# XICIE_AFE_SMD_revC.net
KiCad netlist of a schematic drawn in EAGLE
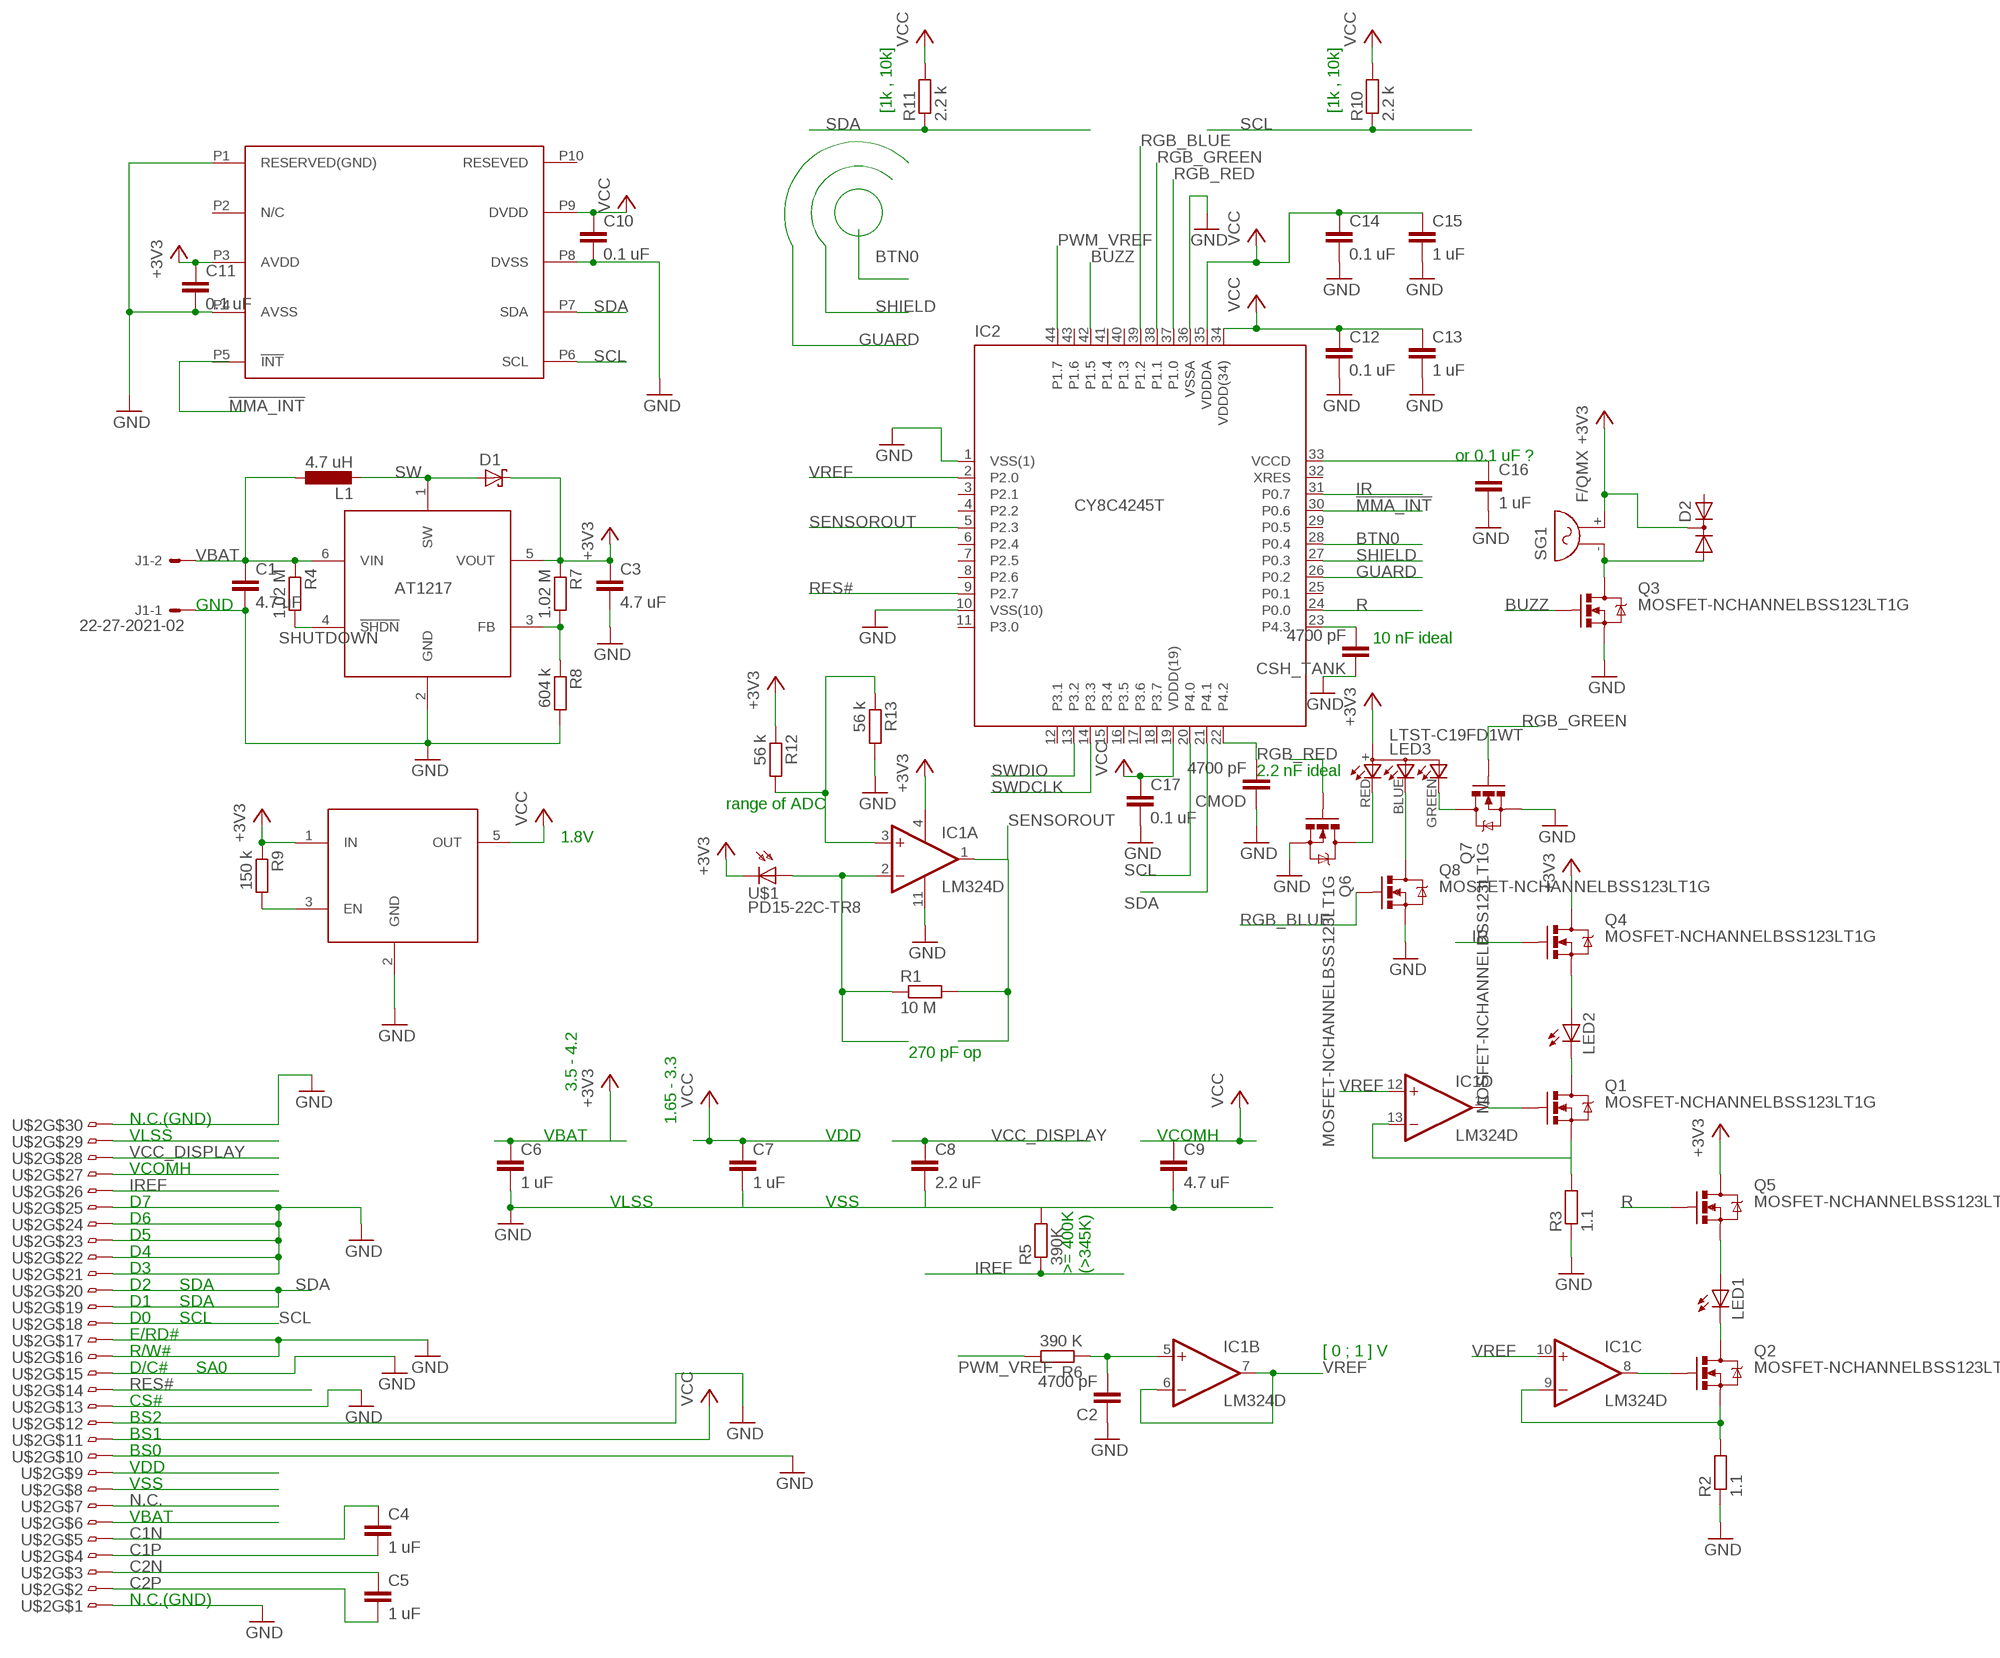
[diagram p0: schematic, sheet 1]

(export (version "E")
  (design (tool "Eeschema 10.0.6"))
  (components
    (comp (ref "C1")
      (value "4.7 uF")
      (footprint "eagle-import:C0603")
      (libsource (lib "eagle-import") (part "C-EUC0603"))
    )
    (comp (ref "C2")
      (value "4700 pF")
      (footprint "eagle-import:C0402")
      (libsource (lib "eagle-import") (part "C-EUC0402"))
    )
    (comp (ref "C3")
      (value "4.7 uF")
      (footprint "eagle-import:C0603")
      (libsource (lib "eagle-import") (part "C-EUC0603"))
    )
    (comp (ref "C4")
      (value "1 uF")
      (footprint "eagle-import:C0402")
      (libsource (lib "eagle-import") (part "C-EUC0402"))
    )
    (comp (ref "C5")
      (value "1 uF")
      (footprint "eagle-import:C0402")
      (libsource (lib "eagle-import") (part "C-EUC0402"))
    )
    (comp (ref "C6")
      (value "1 uF")
      (footprint "eagle-import:C0402")
      (libsource (lib "eagle-import") (part "C-EUC0402"))
    )
    (comp (ref "C7")
      (value "1 uF")
      (footprint "eagle-import:C0402")
      (libsource (lib "eagle-import") (part "C-EUC0402"))
    )
    (comp (ref "C8")
      (value "2.2 uF")
      (footprint "eagle-import:C0603")
      (libsource (lib "eagle-import") (part "C-EUC0603"))
    )
    (comp (ref "C9")
      (value "4.7 uF")
      (footprint "eagle-import:C0603")
      (libsource (lib "eagle-import") (part "C-EUC0603"))
    )
    (comp (ref "C10")
      (value "0.1 uF")
      (footprint "eagle-import:C0402")
      (libsource (lib "eagle-import") (part "C-EUC0402"))
    )
    (comp (ref "C11")
      (value "0.1 uF")
      (footprint "eagle-import:C0402")
      (libsource (lib "eagle-import") (part "C-EUC0402"))
    )
    (comp (ref "C12")
      (value "0.1 uF")
      (footprint "eagle-import:C0402")
      (libsource (lib "eagle-import") (part "C-EUC0402"))
    )
    (comp (ref "C13")
      (value "1 uF")
      (footprint "eagle-import:C0402")
      (libsource (lib "eagle-import") (part "C-EUC0402"))
    )
    (comp (ref "C14")
      (value "0.1 uF")
      (footprint "eagle-import:C0402")
      (libsource (lib "eagle-import") (part "C-EUC0402"))
    )
    (comp (ref "C15")
      (value "1 uF")
      (footprint "eagle-import:C0402")
      (libsource (lib "eagle-import") (part "C-EUC0402"))
    )
    (comp (ref "C16")
      (value "1 uF")
      (footprint "eagle-import:C0402")
      (libsource (lib "eagle-import") (part "C-EUC0402"))
    )
    (comp (ref "C17")
      (value "0.1 uF")
      (footprint "eagle-import:C0402")
      (libsource (lib "eagle-import") (part "C-EUC0402"))
    )
    (comp (ref "CMOD")
      (value "4700 pF")
      (footprint "eagle-import:C0402")
      (libsource (lib "eagle-import") (part "C-EUC0402"))
    )
    (comp (ref "CSH_TANK")
      (value "4700 pF")
      (footprint "eagle-import:C0402")
      (libsource (lib "eagle-import") (part "C-EUC0402"))
    )
    (comp (ref "D1")
      (value "SCHOTTKY-DIODESMD")
      (footprint "eagle-import:SMINI2-F5-B")
      (libsource (lib "eagle-import") (part "SCHOTTKY-DIODESMD"))
    )
    (comp (ref "D2")
      (value "DIODE-2AC|CASOT23")
      (footprint "eagle-import:SOT23")
      (libsource (lib "eagle-import") (part "DIODE-2AC|CASOT23"))
    )
    (comp (ref "IC1")
      (value "LM324D")
      (footprint "eagle-import:SO14")
      (libsource (lib "eagle-import") (part "LM324D"))
    )
    (comp (ref "IC2")
      (value "CY8C4245T")
      (footprint "eagle-import:TQFP44")
      (libsource (lib "eagle-import") (part "CY8C4245T"))
    )
    (comp (ref "IC3")
      (value "AAT1217")
      (footprint "eagle-import:SOT23-6")
      (libsource (lib "eagle-import") (part "AAT1217"))
    )
    (comp (ref "J1")
      (value "22-27-2021-02")
      (footprint "eagle-import:6410-02")
      (libsource (lib "eagle-import") (part "22-?-0227-2021"))
    )
    (comp (ref "L1")
      (value "4.7 uH")
      (footprint "eagle-import:L2518")
      (libsource (lib "eagle-import") (part "L-EU"))
    )
    (comp (ref "LED1")
      (value "LED5MM")
      (footprint "eagle-import:LED5MM")
      (libsource (lib "eagle-import") (part "LED5MM"))
    )
    (comp (ref "LED2")
      (value "LED5MM")
      (footprint "eagle-import:LED5MM")
      (libsource (lib "eagle-import") (part "LED5MM"))
    )
    (comp (ref "LED3")
      (value "LTST-C19FD1WT")
      (footprint "eagle-import:GM1WA55311A")
      (libsource (lib "eagle-import") (part "LTST-C19FD1WT"))
    )
    (comp (ref "Q1")
      (value "MOSFET-NCHANNELBSS123LT1G")
      (footprint "eagle-import:SOT23")
      (libsource (lib "eagle-import") (part "MOSFET-NCHANNELBSS123LT1G"))
    )
    (comp (ref "Q2")
      (value "MOSFET-NCHANNELBSS123LT1G")
      (footprint "eagle-import:SOT23")
      (libsource (lib "eagle-import") (part "MOSFET-NCHANNELBSS123LT1G"))
    )
    (comp (ref "Q3")
      (value "MOSFET-NCHANNELBSS123LT1G")
      (footprint "eagle-import:SOT23")
      (libsource (lib "eagle-import") (part "MOSFET-NCHANNELBSS123LT1G"))
    )
    (comp (ref "Q4")
      (value "MOSFET-NCHANNELBSS123LT1G")
      (footprint "eagle-import:SOT23")
      (libsource (lib "eagle-import") (part "MOSFET-NCHANNELBSS123LT1G"))
    )
    (comp (ref "Q5")
      (value "MOSFET-NCHANNELBSS123LT1G")
      (footprint "eagle-import:SOT23")
      (libsource (lib "eagle-import") (part "MOSFET-NCHANNELBSS123LT1G"))
    )
    (comp (ref "Q6")
      (value "MOSFET-NCHANNELBSS123LT1G")
      (footprint "eagle-import:SOT23")
      (libsource (lib "eagle-import") (part "MOSFET-NCHANNELBSS123LT1G"))
    )
    (comp (ref "Q7")
      (value "MOSFET-NCHANNELBSS123LT1G")
      (footprint "eagle-import:SOT23")
      (libsource (lib "eagle-import") (part "MOSFET-NCHANNELBSS123LT1G"))
    )
    (comp (ref "Q8")
      (value "MOSFET-NCHANNELBSS123LT1G")
      (footprint "eagle-import:SOT23")
      (libsource (lib "eagle-import") (part "MOSFET-NCHANNELBSS123LT1G"))
    )
    (comp (ref "R1")
      (value "10 M")
      (footprint "eagle-import:R0402")
      (libsource (lib "eagle-import") (part "R-EU_R0402"))
    )
    (comp (ref "R2")
      (value "1.1")
      (footprint "eagle-import:R0402")
      (libsource (lib "eagle-import") (part "R-EU_R0402"))
    )
    (comp (ref "R3")
      (value "1.1")
      (footprint "eagle-import:R0402")
      (libsource (lib "eagle-import") (part "R-EU_R0402"))
    )
    (comp (ref "R4")
      (value "1.02 M")
      (footprint "eagle-import:R0805")
      (libsource (lib "eagle-import") (part "R-EU_R0805"))
    )
    (comp (ref "R5")
      (value "390K")
      (footprint "eagle-import:R0603")
      (libsource (lib "eagle-import") (part "resistor_R-EU_R0603"))
    )
    (comp (ref "R6")
      (value "390 K")
      (footprint "eagle-import:R0603")
      (libsource (lib "eagle-import") (part "R-EU_R0603"))
    )
    (comp (ref "R7")
      (value "1.02 M")
      (footprint "eagle-import:R0805")
      (libsource (lib "eagle-import") (part "R-EU_R0805"))
    )
    (comp (ref "R8")
      (value "604 k")
      (footprint "eagle-import:R0603")
      (libsource (lib "eagle-import") (part "R-EU_R0603"))
    )
    (comp (ref "R9")
      (value "150 k")
      (footprint "eagle-import:R0603")
      (libsource (lib "eagle-import") (part "R-EU_R0603"))
    )
    (comp (ref "R10")
      (value "2.2 k")
      (footprint "eagle-import:R0402")
      (libsource (lib "eagle-import") (part "R-EU_R0402"))
    )
    (comp (ref "R11")
      (value "2.2 k")
      (footprint "eagle-import:R0402")
      (libsource (lib "eagle-import") (part "R-EU_R0402"))
    )
    (comp (ref "R12")
      (value "56 k")
      (footprint "eagle-import:R0603")
      (libsource (lib "eagle-import") (part "R-EU_R0603"))
    )
    (comp (ref "R13")
      (value "56 k")
      (footprint "eagle-import:R0603")
      (libsource (lib "eagle-import") (part "R-EU_R0603"))
    )
    (comp (ref "SG1")
      (value "F/QMX")
      (footprint "eagle-import:F_QMX")
      (libsource (lib "eagle-import") (part "F/QMX"))
    )
    (comp (ref "U$1")
      (value "PD15-22C-TR8")
      (footprint "eagle-import:PHOTO_SMD")
      (libsource (lib "eagle-import") (part "PD15-22C-TR8"))
    )
    (comp (ref "U$2")
      (value "ER-OLED0.96")
      (footprint "eagle-import:FLEX0.7X30")
      (libsource (lib "eagle-import") (part "ER-OLED0.96"))
    )
    (comp (ref "U$3")
      (value "AAT3221")
      (footprint "eagle-import:SOT23-5")
      (libsource (lib "eagle-import") (part "AAT3221"))
    )
    (comp (ref "U$4")
      (value "MMA7660FC")
      (footprint "eagle-import:DFN10")
      (libsource (lib "eagle-import") (part "MMA7660FC"))
    )
  )
  (nets
    (net (code "1") (name "+3V3") (class "Default")
      (node (ref "C11") (pin "1") (pinfunction "1_1") (pintype "passive"))
      (node (ref "C3") (pin "1") (pinfunction "1_1") (pintype "passive"))
      (node (ref "C6") (pin "1") (pinfunction "1_1") (pintype "passive"))
      (node (ref "D1") (pin "C") (pinfunction "C_C") (pintype "passive"))
      (node (ref "D2") (pin "3") (pinfunction "C_3") (pintype "passive"))
      (node (ref "IC1") (pin "4") (pinfunction "V+_4") (pintype "power_in"))
      (node (ref "IC3") (pin "5") (pinfunction "VOUT_5") (pintype "bidirectional"))
      (node (ref "LED3") (pin "+") (pinfunction "A_+") (pintype "passive"))
      (node (ref "Q4") (pin "3") (pinfunction "D_3") (pintype "passive"))
      (node (ref "Q5") (pin "3") (pinfunction "D_3") (pintype "passive"))
      (node (ref "R12") (pin "1") (pinfunction "1_1") (pintype "passive"))
      (node (ref "R7") (pin "1") (pinfunction "1_1") (pintype "passive"))
      (node (ref "R9") (pin "1") (pinfunction "1_1") (pintype "passive"))
      (node (ref "SG1") (pin "+") (pinfunction "2_+") (pintype "passive"))
      (node (ref "U$1") (pin "CATHODE1") (pinfunction "C_CATHODE1") (pintype "passive"))
      (node (ref "U$1") (pin "CATHODE2") (pinfunction "C_CATHODE2") (pintype "passive"))
      (node (ref "U$2") (pin "P6") (pinfunction "1_P6") (pintype "passive"))
      (node (ref "U$3") (pin "1") (pinfunction "IN_1") (pintype "bidirectional"))
      (node (ref "U$4") (pin "P3") (pinfunction "AVDD_P3") (pintype "bidirectional"))
    )
    (net (code "2") (name "/BTN0") (class "Default")
      (node (ref "IC2") (pin "28") (pinfunction "P0.4_28") (pintype "bidirectional"))
    )
    (net (code "3") (name "/BUZZ") (class "Default")
      (node (ref "IC2") (pin "42") (pinfunction "P1.5_42") (pintype "bidirectional"))
      (node (ref "Q3") (pin "1") (pinfunction "G_1") (pintype "passive"))
    )
    (net (code "4") (name "/C1N") (class "Default")
      (node (ref "C4") (pin "1") (pinfunction "1_1") (pintype "passive"))
      (node (ref "U$2") (pin "P5") (pinfunction "1_P5") (pintype "passive"))
    )
    (net (code "5") (name "/C1P") (class "Default")
      (node (ref "C4") (pin "2") (pinfunction "2_2") (pintype "passive"))
      (node (ref "U$2") (pin "P4") (pinfunction "1_P4") (pintype "passive"))
    )
    (net (code "6") (name "/C2N") (class "Default")
      (node (ref "C5") (pin "1") (pinfunction "1_1") (pintype "passive"))
      (node (ref "U$2") (pin "P3") (pinfunction "1_P3") (pintype "passive"))
    )
    (net (code "7") (name "/C2P") (class "Default")
      (node (ref "C5") (pin "2") (pinfunction "2_2") (pintype "passive"))
      (node (ref "U$2") (pin "P2") (pinfunction "1_P2") (pintype "passive"))
    )
    (net (code "8") (name "/GUARD") (class "Default")
      (node (ref "IC2") (pin "26") (pinfunction "P0.2_26") (pintype "input"))
    )
    (net (code "9") (name "/IR") (class "Default")
      (node (ref "IC2") (pin "31") (pinfunction "P0.7_31") (pintype "bidirectional"))
      (node (ref "Q4") (pin "1") (pinfunction "G_1") (pintype "passive"))
    )
    (net (code "10") (name "/IREF") (class "Default")
      (node (ref "R5") (pin "1") (pinfunction "1_1") (pintype "passive"))
      (node (ref "U$2") (pin "P26") (pinfunction "1_P26") (pintype "passive"))
    )
    (net (code "11") (name "/N.C.") (class "Default")
      (node (ref "U$2") (pin "P7") (pinfunction "1_P7") (pintype "passive"))
    )
    (net (code "12") (name "/P2.2") (class "Default")
      (node (ref "IC2") (pin "4") (pinfunction "P2.2_4") (pintype "power_in"))
    )
    (net (code "13") (name "/P2.6") (class "Default")
      (node (ref "IC2") (pin "8") (pinfunction "P2.6_8") (pintype "power_in"))
    )
    (net (code "14") (name "/P3.6") (class "Default")
      (node (ref "IC2") (pin "17") (pinfunction "P3.6_17") (pintype "power_in"))
    )
    (net (code "15") (name "/PWM_VREF") (class "Default")
      (node (ref "IC2") (pin "44") (pinfunction "P1.7_44") (pintype "bidirectional"))
      (node (ref "R6") (pin "2") (pinfunction "2_2") (pintype "passive"))
    )
    (net (code "16") (name "/R") (class "Default")
      (node (ref "IC2") (pin "24") (pinfunction "P0.0_24") (pintype "bidirectional"))
      (node (ref "Q5") (pin "1") (pinfunction "G_1") (pintype "passive"))
    )
    (net (code "17") (name "/RES#") (class "Default")
      (node (ref "IC2") (pin "9") (pinfunction "P2.7_9") (pintype "bidirectional"))
      (node (ref "U$2") (pin "P14") (pinfunction "1_P14") (pintype "passive"))
    )
    (net (code "18") (name "/RGB_BLUE") (class "Default")
      (node (ref "IC2") (pin "39") (pinfunction "P1.2_39") (pintype "power_in"))
      (node (ref "Q8") (pin "1") (pinfunction "G_1") (pintype "passive"))
    )
    (net (code "19") (name "/RGB_GREEN") (class "Default")
      (node (ref "IC2") (pin "38") (pinfunction "P1.1_38") (pintype "bidirectional"))
      (node (ref "Q7") (pin "1") (pinfunction "G_1") (pintype "passive"))
    )
    (net (code "20") (name "/RGB_RED") (class "Default")
      (node (ref "IC2") (pin "37") (pinfunction "P1.0_37") (pintype "bidirectional"))
      (node (ref "Q6") (pin "1") (pinfunction "G_1") (pintype "passive"))
    )
    (net (code "21") (name "/SCL") (class "Default")
      (node (ref "IC2") (pin "20") (pinfunction "P4.0_20") (pintype "bidirectional"))
      (node (ref "R10") (pin "1") (pinfunction "1_1") (pintype "passive"))
      (node (ref "U$2") (pin "P18") (pinfunction "1_P18") (pintype "passive"))
      (node (ref "U$4") (pin "P6") (pinfunction "SCL_P6") (pintype "bidirectional"))
    )
    (net (code "22") (name "/SDA") (class "Default")
      (node (ref "IC2") (pin "21") (pinfunction "P4.1_21") (pintype "bidirectional"))
      (node (ref "R11") (pin "1") (pinfunction "1_1") (pintype "passive"))
      (node (ref "U$2") (pin "P19") (pinfunction "1_P19") (pintype "passive"))
      (node (ref "U$2") (pin "P20") (pinfunction "1_P20") (pintype "passive"))
      (node (ref "U$4") (pin "P7") (pinfunction "SDA_P7") (pintype "bidirectional"))
    )
    (net (code "23") (name "/SENSOROUT") (class "Default")
      (node (ref "IC1") (pin "1") (pinfunction "OUT_1") (pintype "output"))
      (node (ref "IC2") (pin "5") (pinfunction "P2.3_5") (pintype "bidirectional"))
      (node (ref "R1") (pin "2") (pinfunction "2_2") (pintype "passive"))
    )
    (net (code "24") (name "/SHIELD") (class "Default")
      (node (ref "IC2") (pin "27") (pinfunction "P0.3_27") (pintype "bidirectional"))
    )
    (net (code "25") (name "/SHUTDOWN") (class "Default")
      (node (ref "IC3") (pin "4") (pinfunction "~{SHDN}_4") (pintype "bidirectional"))
      (node (ref "R4") (pin "2") (pinfunction "2_2") (pintype "passive"))
    )
    (net (code "26") (name "/SW") (class "Default")
      (node (ref "D1") (pin "A") (pinfunction "A_A") (pintype "passive"))
      (node (ref "IC3") (pin "1") (pinfunction "SW_1") (pintype "bidirectional"))
      (node (ref "L1") (pin "2") (pinfunction "2_2") (pintype "passive"))
    )
    (net (code "27") (name "/SWDCLK") (class "Default")
      (node (ref "IC2") (pin "14") (pinfunction "P3.3_14") (pintype "bidirectional"))
    )
    (net (code "28") (name "/SWDIO") (class "Default")
      (node (ref "IC2") (pin "13") (pinfunction "P3.2_13") (pintype "bidirectional"))
    )
    (net (code "29") (name "/VBAT") (class "Default")
      (node (ref "C1") (pin "1") (pinfunction "1_1") (pintype "passive"))
      (node (ref "IC3") (pin "6") (pinfunction "VIN_6") (pintype "bidirectional"))
      (node (ref "J1") (pin "2") (pinfunction "S_2") (pintype "passive"))
      (node (ref "L1") (pin "1") (pinfunction "1_1") (pintype "passive"))
      (node (ref "R4") (pin "1") (pinfunction "1_1") (pintype "passive"))
    )
    (net (code "30") (name "/VCC_DISPLAY") (class "Default")
      (node (ref "C8") (pin "1") (pinfunction "1_1") (pintype "passive"))
      (node (ref "U$2") (pin "P28") (pinfunction "1_P28") (pintype "passive"))
    )
    (net (code "31") (name "/VREF") (class "Default")
      (node (ref "IC1") (pin "10") (pinfunction "+IN_10") (pintype "input"))
      (node (ref "IC1") (pin "12") (pinfunction "+IN_12") (pintype "input"))
      (node (ref "IC1") (pin "6") (pinfunction "-IN_6") (pintype "input"))
      (node (ref "IC1") (pin "7") (pinfunction "OUT_7") (pintype "output"))
      (node (ref "IC2") (pin "2") (pinfunction "P2.0_2") (pintype "bidirectional"))
    )
    (net (code "32") (name "/~{MMA_INT}") (class "Default")
      (node (ref "IC2") (pin "30") (pinfunction "P0.6_30") (pintype "power_in"))
    )
    (net (code "33") (name "GND") (class "Default")
      (node (ref "C1") (pin "2") (pinfunction "2_2") (pintype "passive"))
      (node (ref "C10") (pin "2") (pinfunction "2_2") (pintype "passive"))
      (node (ref "C11") (pin "2") (pinfunction "2_2") (pintype "passive"))
      (node (ref "C12") (pin "2") (pinfunction "2_2") (pintype "passive"))
      (node (ref "C13") (pin "2") (pinfunction "2_2") (pintype "passive"))
      (node (ref "C14") (pin "2") (pinfunction "2_2") (pintype "passive"))
      (node (ref "C15") (pin "2") (pinfunction "2_2") (pintype "passive"))
      (node (ref "C16") (pin "2") (pinfunction "2_2") (pintype "passive"))
      (node (ref "C17") (pin "2") (pinfunction "2_2") (pintype "passive"))
      (node (ref "C2") (pin "1") (pinfunction "1_1") (pintype "passive"))
      (node (ref "C3") (pin "2") (pinfunction "2_2") (pintype "passive"))
      (node (ref "C6") (pin "2") (pinfunction "2_2") (pintype "passive"))
      (node (ref "C7") (pin "2") (pinfunction "2_2") (pintype "passive"))
      (node (ref "C8") (pin "2") (pinfunction "2_2") (pintype "passive"))
      (node (ref "C9") (pin "2") (pinfunction "2_2") (pintype "passive"))
      (node (ref "CMOD") (pin "1") (pinfunction "1_1") (pintype "passive"))
      (node (ref "CSH_TANK") (pin "1") (pinfunction "1_1") (pintype "passive"))
      (node (ref "IC1") (pin "11") (pinfunction "V-_11") (pintype "power_in"))
      (node (ref "IC2") (pin "1") (pinfunction "VSS(1)_1") (pintype "bidirectional"))
      (node (ref "IC2") (pin "10") (pinfunction "VSS(10)_10") (pintype "bidirectional"))
      (node (ref "IC2") (pin "36") (pinfunction "VSSA_36") (pintype "bidirectional"))
      (node (ref "IC3") (pin "2") (pinfunction "GND_2") (pintype "bidirectional"))
      (node (ref "J1") (pin "1") (pinfunction "S_1") (pintype "passive"))
      (node (ref "Q3") (pin "2") (pinfunction "S_2") (pintype "passive"))
      (node (ref "Q6") (pin "2") (pinfunction "S_2") (pintype "passive"))
      (node (ref "Q7") (pin "2") (pinfunction "S_2") (pintype "passive"))
      (node (ref "Q8") (pin "2") (pinfunction "S_2") (pintype "passive"))
      (node (ref "R13") (pin "2") (pinfunction "2_2") (pintype "passive"))
      (node (ref "R2") (pin "1") (pinfunction "1_1") (pintype "passive"))
      (node (ref "R3") (pin "1") (pinfunction "1_1") (pintype "passive"))
      (node (ref "R5") (pin "2") (pinfunction "2_2") (pintype "passive"))
      (node (ref "R8") (pin "2") (pinfunction "2_2") (pintype "passive"))
      (node (ref "U$2") (pin "P1") (pinfunction "1_P1") (pintype "passive"))
      (node (ref "U$2") (pin "P10") (pinfunction "1_P10") (pintype "passive"))
      (node (ref "U$2") (pin "P12") (pinfunction "1_P12") (pintype "passive"))
      (node (ref "U$2") (pin "P13") (pinfunction "1_P13") (pintype "passive"))
      (node (ref "U$2") (pin "P15") (pinfunction "1_P15") (pintype "passive"))
      (node (ref "U$2") (pin "P16") (pinfunction "1_P16") (pintype "passive"))
      (node (ref "U$2") (pin "P17") (pinfunction "1_P17") (pintype "passive"))
      (node (ref "U$2") (pin "P21") (pinfunction "1_P21") (pintype "passive"))
      (node (ref "U$2") (pin "P22") (pinfunction "1_P22") (pintype "passive"))
      (node (ref "U$2") (pin "P23") (pinfunction "1_P23") (pintype "passive"))
      (node (ref "U$2") (pin "P24") (pinfunction "1_P24") (pintype "passive"))
      (node (ref "U$2") (pin "P25") (pinfunction "1_P25") (pintype "passive"))
      (node (ref "U$2") (pin "P29") (pinfunction "1_P29") (pintype "passive"))
      (node (ref "U$2") (pin "P30") (pinfunction "1_P30") (pintype "passive"))
      (node (ref "U$2") (pin "P8") (pinfunction "1_P8") (pintype "passive"))
      (node (ref "U$3") (pin "2") (pinfunction "GND_2") (pintype "bidirectional"))
      (node (ref "U$4") (pin "P1") (pinfunction "RESERVED(GND)_P1") (pintype "bidirectional"))
      (node (ref "U$4") (pin "P4") (pinfunction "AVSS_P4") (pintype "bidirectional"))
      (node (ref "U$4") (pin "P8") (pinfunction "DVSS_P8") (pintype "bidirectional"))
    )
    (net (code "34") (name "Net-(D2-A1)") (class "Default")
      (node (ref "D2") (pin "1") (pinfunction "A1_1") (pintype "passive"))
      (node (ref "Q3") (pin "3") (pinfunction "D_3") (pintype "passive"))
      (node (ref "SG1") (pin "-") (pinfunction "1_-") (pintype "passive"))
    )
    (net (code "35") (name "Net-(IC1A-+IN)") (class "Default")
      (node (ref "IC1") (pin "3") (pinfunction "+IN_3") (pintype "input"))
      (node (ref "R12") (pin "2") (pinfunction "2_2") (pintype "passive"))
      (node (ref "R13") (pin "1") (pinfunction "1_1") (pintype "passive"))
    )
    (net (code "36") (name "Net-(IC1A--IN)") (class "Default")
      (node (ref "IC1") (pin "2") (pinfunction "-IN_2") (pintype "input"))
      (node (ref "R1") (pin "1") (pinfunction "1_1") (pintype "passive"))
      (node (ref "U$1") (pin "ANODE1") (pinfunction "A_ANODE1") (pintype "passive"))
      (node (ref "U$1") (pin "ANODE2") (pinfunction "A_ANODE2") (pintype "passive"))
    )
    (net (code "37") (name "Net-(IC1B-+IN)") (class "Default")
      (node (ref "C2") (pin "2") (pinfunction "2_2") (pintype "passive"))
      (node (ref "IC1") (pin "5") (pinfunction "+IN_5") (pintype "input"))
      (node (ref "R6") (pin "1") (pinfunction "1_1") (pintype "passive"))
    )
    (net (code "38") (name "Net-(IC1C--IN)") (class "Default")
      (node (ref "IC1") (pin "9") (pinfunction "-IN_9") (pintype "input"))
      (node (ref "Q2") (pin "2") (pinfunction "S_2") (pintype "passive"))
      (node (ref "R2") (pin "2") (pinfunction "2_2") (pintype "passive"))
    )
    (net (code "39") (name "Net-(IC1C-OUT)") (class "Default")
      (node (ref "IC1") (pin "8") (pinfunction "OUT_8") (pintype "output"))
      (node (ref "Q2") (pin "1") (pinfunction "G_1") (pintype "passive"))
    )
    (net (code "40") (name "Net-(IC1D--IN)") (class "Default")
      (node (ref "IC1") (pin "13") (pinfunction "-IN_13") (pintype "input"))
      (node (ref "Q1") (pin "2") (pinfunction "S_2") (pintype "passive"))
      (node (ref "R3") (pin "2") (pinfunction "2_2") (pintype "passive"))
    )
    (net (code "41") (name "Net-(IC1D-OUT)") (class "Default")
      (node (ref "IC1") (pin "14") (pinfunction "OUT_14") (pintype "output"))
      (node (ref "Q1") (pin "1") (pinfunction "G_1") (pintype "passive"))
    )
    (net (code "42") (name "Net-(IC2-P4.2)") (class "Default")
      (node (ref "CMOD") (pin "2") (pinfunction "2_2") (pintype "passive"))
      (node (ref "IC2") (pin "22") (pinfunction "P4.2_22") (pintype "bidirectional"))
    )
    (net (code "43") (name "Net-(IC2-P4.3)") (class "Default")
      (node (ref "CSH_TANK") (pin "2") (pinfunction "2_2") (pintype "passive"))
      (node (ref "IC2") (pin "23") (pinfunction "P4.3_23") (pintype "bidirectional"))
    )
    (net (code "44") (name "Net-(IC2-VCCD)") (class "Default")
      (node (ref "C16") (pin "1") (pinfunction "1_1") (pintype "passive"))
      (node (ref "IC2") (pin "33") (pinfunction "VCCD_33") (pintype "bidirectional"))
    )
    (net (code "45") (name "Net-(IC3-FB)") (class "Default")
      (node (ref "IC3") (pin "3") (pinfunction "FB_3") (pintype "bidirectional"))
      (node (ref "R7") (pin "2") (pinfunction "2_2") (pintype "passive"))
      (node (ref "R8") (pin "1") (pinfunction "1_1") (pintype "passive"))
    )
    (net (code "46") (name "Net-(LED1-C)") (class "Default")
      (node (ref "LED1") (pin "K") (pinfunction "C_K") (pintype "passive"))
      (node (ref "Q2") (pin "3") (pinfunction "D_3") (pintype "passive"))
    )
    (net (code "47") (name "Net-(LED2-C)") (class "Default")
      (node (ref "LED2") (pin "K") (pinfunction "C_K") (pintype "passive"))
      (node (ref "Q1") (pin "3") (pinfunction "D_3") (pintype "passive"))
    )
    (net (code "48") (name "Net-(LED3-CBLUE)") (class "Default")
      (node (ref "LED3") (pin "BLUE") (pinfunction "CBLUE_BLUE") (pintype "passive"))
      (node (ref "Q8") (pin "3") (pinfunction "D_3") (pintype "passive"))
    )
    (net (code "49") (name "Net-(LED3-CGREEN)") (class "Default")
      (node (ref "LED3") (pin "GREEN") (pinfunction "CGREEN_GREEN") (pintype "passive"))
      (node (ref "Q7") (pin "3") (pinfunction "D_3") (pintype "passive"))
    )
    (net (code "50") (name "Net-(LED3-CRED)") (class "Default")
      (node (ref "LED3") (pin "RED") (pinfunction "CRED_RED") (pintype "passive"))
      (node (ref "Q6") (pin "3") (pinfunction "D_3") (pintype "passive"))
    )
    (net (code "51") (name "Net-(Q4-S)") (class "Default")
      (node (ref "LED2") (pin "A") (pinfunction "A_A") (pintype "passive"))
      (node (ref "Q4") (pin "2") (pinfunction "S_2") (pintype "passive"))
    )
    (net (code "52") (name "Net-(Q5-S)") (class "Default")
      (node (ref "LED1") (pin "A") (pinfunction "A_A") (pintype "passive"))
      (node (ref "Q5") (pin "2") (pinfunction "S_2") (pintype "passive"))
    )
    (net (code "53") (name "Net-(U$3-EN)") (class "Default")
      (node (ref "R9") (pin "2") (pinfunction "2_2") (pintype "passive"))
      (node (ref "U$3") (pin "3") (pinfunction "EN_3") (pintype "bidirectional"))
    )
    (net (code "54") (name "VCC") (class "Default")
      (node (ref "C10") (pin "1") (pinfunction "1_1") (pintype "passive"))
      (node (ref "C12") (pin "1") (pinfunction "1_1") (pintype "passive"))
      (node (ref "C13") (pin "1") (pinfunction "1_1") (pintype "passive"))
      (node (ref "C14") (pin "1") (pinfunction "1_1") (pintype "passive"))
      (node (ref "C15") (pin "1") (pinfunction "1_1") (pintype "passive"))
      (node (ref "C17") (pin "1") (pinfunction "1_1") (pintype "passive"))
      (node (ref "C7") (pin "1") (pinfunction "1_1") (pintype "passive"))
      (node (ref "C9") (pin "1") (pinfunction "1_1") (pintype "passive"))
      (node (ref "IC2") (pin "19") (pinfunction "VDDD(19)_19") (pintype "bidirectional"))
      (node (ref "IC2") (pin "34") (pinfunction "VDDD(34)_34") (pintype "bidirectional"))
      (node (ref "IC2") (pin "35") (pinfunction "VDDDA_35") (pintype "bidirectional"))
      (node (ref "R10") (pin "2") (pinfunction "2_2") (pintype "passive"))
      (node (ref "R11") (pin "2") (pinfunction "2_2") (pintype "passive"))
      (node (ref "U$2") (pin "P11") (pinfunction "1_P11") (pintype "passive"))
      (node (ref "U$2") (pin "P27") (pinfunction "1_P27") (pintype "passive"))
      (node (ref "U$2") (pin "P9") (pinfunction "1_P9") (pintype "passive"))
      (node (ref "U$3") (pin "5") (pinfunction "OUT_5") (pintype "bidirectional"))
      (node (ref "U$4") (pin "P9") (pinfunction "DVDD_P9") (pintype "bidirectional"))
    )
    (net (code "55") (name "unconnected-(D2-A2-Pad2)") (class "Default")
      (node (ref "D2") (pin "2") (pinfunction "A2_2") (pintype "passive"))
    )
    (net (code "56") (name "unconnected-(IC2-P0.1-Pad25)") (class "Default")
      (node (ref "IC2") (pin "25") (pinfunction "P0.1_25") (pintype "bidirectional"))
    )
    (net (code "57") (name "unconnected-(IC2-P0.5-Pad29)") (class "Default")
      (node (ref "IC2") (pin "29") (pinfunction "P0.5_29") (pintype "bidirectional"))
    )
    (net (code "58") (name "unconnected-(IC2-P1.3-Pad40)") (class "Default")
      (node (ref "IC2") (pin "40") (pinfunction "P1.3_40") (pintype "bidirectional"))
    )
    (net (code "59") (name "unconnected-(IC2-P1.4-Pad41)") (class "Default")
      (node (ref "IC2") (pin "41") (pinfunction "P1.4_41") (pintype "bidirectional"))
    )
    (net (code "60") (name "unconnected-(IC2-P1.6-Pad43)") (class "Default")
      (node (ref "IC2") (pin "43") (pinfunction "P1.6_43") (pintype "bidirectional"))
    )
    (net (code "61") (name "unconnected-(IC2-P2.1-Pad3)") (class "Default")
      (node (ref "IC2") (pin "3") (pinfunction "P2.1_3") (pintype "bidirectional"))
    )
    (net (code "62") (name "unconnected-(IC2-P2.4-Pad6)") (class "Default")
      (node (ref "IC2") (pin "6") (pinfunction "P2.4_6") (pintype "bidirectional"))
    )
    (net (code "63") (name "unconnected-(IC2-P2.5-Pad7)") (class "Default")
      (node (ref "IC2") (pin "7") (pinfunction "P2.5_7") (pintype "bidirectional"))
    )
    (net (code "64") (name "unconnected-(IC2-P3.0-Pad11)") (class "Default")
      (node (ref "IC2") (pin "11") (pinfunction "P3.0_11") (pintype "bidirectional"))
    )
    (net (code "65") (name "unconnected-(IC2-P3.1-Pad12)") (class "Default")
      (node (ref "IC2") (pin "12") (pinfunction "P3.1_12") (pintype "bidirectional"))
    )
    (net (code "66") (name "unconnected-(IC2-P3.4-Pad15)") (class "Default")
      (node (ref "IC2") (pin "15") (pinfunction "P3.4_15") (pintype "bidirectional"))
    )
    (net (code "67") (name "unconnected-(IC2-P3.5-Pad16)") (class "Default")
      (node (ref "IC2") (pin "16") (pinfunction "P3.5_16") (pintype "bidirectional"))
    )
    (net (code "68") (name "unconnected-(IC2-P3.7-Pad18)") (class "Default")
      (node (ref "IC2") (pin "18") (pinfunction "P3.7_18") (pintype "bidirectional"))
    )
    (net (code "69") (name "unconnected-(IC2-XRES-Pad32)") (class "Default")
      (node (ref "IC2") (pin "32") (pinfunction "XRES_32") (pintype "bidirectional"))
    )
    (net (code "70") (name "unconnected-(U$4-N{slash}C-PadP2)") (class "Default")
      (node (ref "U$4") (pin "P2") (pinfunction "N/C_P2") (pintype "bidirectional"))
    )
    (net (code "71") (name "unconnected-(U$4-RESEVED-PadP10)") (class "Default")
      (node (ref "U$4") (pin "P10") (pinfunction "RESEVED_P10") (pintype "bidirectional"))
    )
    (net (code "72") (name "unconnected-(U$4-~{INT}-PadP5)") (class "Default")
      (node (ref "U$4") (pin "P5") (pinfunction "~{INT}_P5") (pintype "bidirectional"))
    )
  )
)
